# V0_24.net
KiCad netlist of a schematic drawn in EAGLE
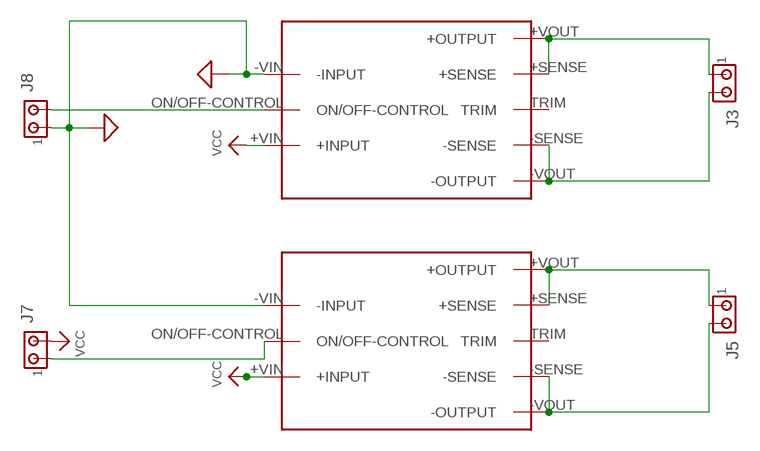
[diagram p0: schematic, sheet 1]

(export (version "E")
  (design (tool "Eeschema 10.0.6"))
  (components
    (comp (ref "J3")
      (value "MTA02-156")
      (footprint "eagle-import:MYJUMPER")
      (libsource (lib "eagle-import") (part "MTA02-156"))
    )
    (comp (ref "J5")
      (value "MTA02-156")
      (footprint "eagle-import:MYJUMPER")
      (libsource (lib "eagle-import") (part "MTA02-156"))
    )
    (comp (ref "J7")
      (value "MTA02-156")
      (footprint "eagle-import:MYJUMPER")
      (libsource (lib "eagle-import") (part "MTA02-156"))
    )
    (comp (ref "J8")
      (value "MTA02-156")
      (footprint "eagle-import:MYJUMPER")
      (libsource (lib "eagle-import") (part "MTA02-156"))
    )
    (comp (ref "U$3")
      (value "DC/DC_CONV_24V")
      (footprint "eagle-import:UWE")
      (libsource (lib "eagle-import") (part "DC/DC_CONV_24V"))
    )
    (comp (ref "U$4")
      (value "DC/DC_CONV_24V")
      (footprint "eagle-import:UWE")
      (libsource (lib "eagle-import") (part "DC/DC_CONV_24V"))
    )
  )
  (nets
    (net (code "1") (name "Net-(J7-Pad1)") (class "Default")
      (node (ref "J7") (pin "1") (pinfunction "1_1") (pintype "passive"))
      (node (ref "U$4") (pin "ON/OFF-CONTROL") (pinfunction "ON/OFF-CONTROL_ON/OFF-CONTROL") (pintype "bidirectional"))
    )
    (net (code "2") (name "Net-(J8-Pad2)") (class "Default")
      (node (ref "J8") (pin "2") (pinfunction "2_2") (pintype "passive"))
      (node (ref "U$3") (pin "ON/OFF-CONTROL") (pinfunction "ON/OFF-CONTROL_ON/OFF-CONTROL") (pintype "bidirectional"))
    )
    (net (code "3") (name "Net-(U$3-+OUTPUT)") (class "Default")
      (node (ref "J3") (pin "1") (pinfunction "1_1") (pintype "passive"))
      (node (ref "U$3") (pin "+SENSE") (pinfunction "+SENSE_+SENSE") (pintype "bidirectional"))
      (node (ref "U$3") (pin "+VOUT") (pinfunction "+OUTPUT_+VOUT") (pintype "bidirectional"))
    )
    (net (code "4") (name "Net-(U$3--OUTPUT)") (class "Default")
      (node (ref "J3") (pin "2") (pinfunction "2_2") (pintype "passive"))
      (node (ref "U$3") (pin "-SENSE") (pinfunction "-SENSE_-SENSE") (pintype "bidirectional"))
      (node (ref "U$3") (pin "-VOUT") (pinfunction "-OUTPUT_-VOUT") (pintype "bidirectional"))
    )
    (net (code "5") (name "Net-(U$4-+OUTPUT)") (class "Default")
      (node (ref "J5") (pin "1") (pinfunction "1_1") (pintype "passive"))
      (node (ref "U$4") (pin "+SENSE") (pinfunction "+SENSE_+SENSE") (pintype "bidirectional"))
      (node (ref "U$4") (pin "+VOUT") (pinfunction "+OUTPUT_+VOUT") (pintype "bidirectional"))
    )
    (net (code "6") (name "Net-(U$4--OUTPUT)") (class "Default")
      (node (ref "J5") (pin "2") (pinfunction "2_2") (pintype "passive"))
      (node (ref "U$4") (pin "-SENSE") (pinfunction "-SENSE_-SENSE") (pintype "bidirectional"))
      (node (ref "U$4") (pin "-VOUT") (pinfunction "-OUTPUT_-VOUT") (pintype "bidirectional"))
    )
    (net (code "7") (name "SUP") (class "Default")
      (node (ref "J8") (pin "1") (pinfunction "1_1") (pintype "passive"))
      (node (ref "U$3") (pin "-VIN") (pinfunction "-INPUT_-VIN") (pintype "bidirectional"))
      (node (ref "U$4") (pin "-VIN") (pinfunction "-INPUT_-VIN") (pintype "bidirectional"))
    )
    (net (code "8") (name "VCC") (class "Default")
      (node (ref "J7") (pin "2") (pinfunction "2_2") (pintype "passive"))
      (node (ref "U$3") (pin "+VIN") (pinfunction "+INPUT_+VIN") (pintype "bidirectional"))
      (node (ref "U$4") (pin "+VIN") (pinfunction "+INPUT_+VIN") (pintype "bidirectional"))
    )
    (net (code "9") (name "unconnected-(U$3-PadTRIM)") (class "Default")
      (node (ref "U$3") (pin "TRIM") (pinfunction "TRIM_TRIM") (pintype "bidirectional"))
    )
    (net (code "10") (name "unconnected-(U$4-PadTRIM)") (class "Default")
      (node (ref "U$4") (pin "TRIM") (pinfunction "TRIM_TRIM") (pintype "bidirectional"))
    )
  )
)
